# PLmodule.net
KiCad netlist of a schematic drawn in Altium Designer
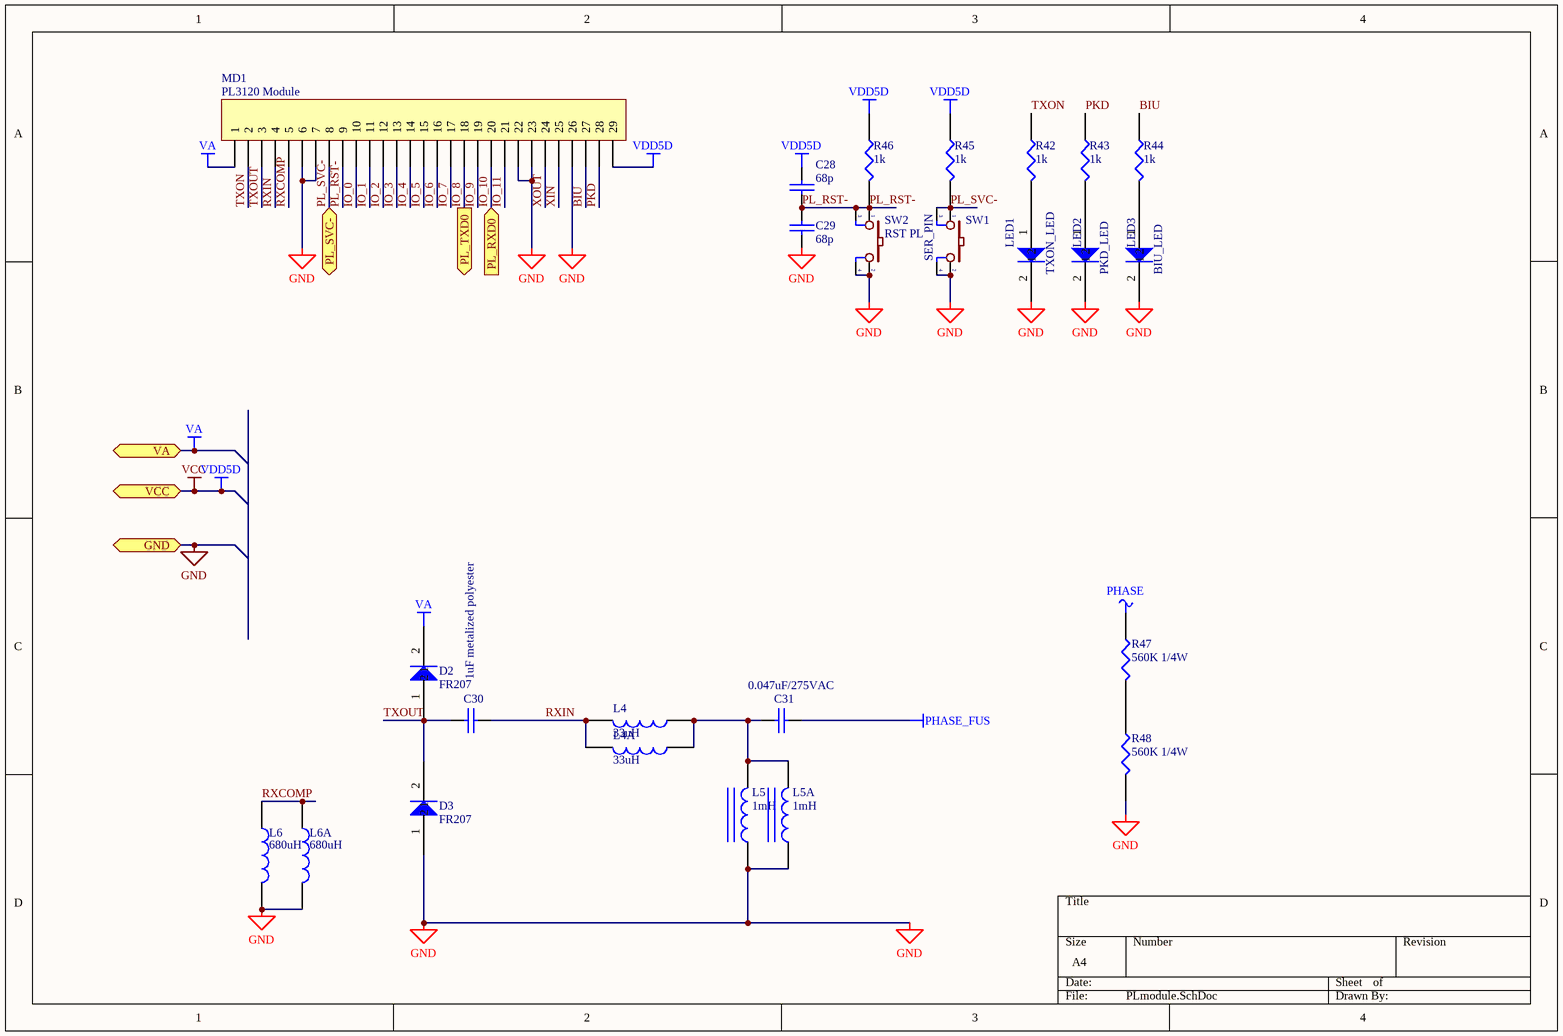
[diagram p0: PLmodule.SchDoc]

(export (version "E")
  (design (tool "Eeschema 10.0.6"))
  (components
    (comp (ref "C28")
      (value "68p")
      (footprint "C6-0805_N")
      (description "Capacitor")
      (libsource (lib "*") (part "CAP"))
    )
    (comp (ref "C29")
      (value "68p")
      (footprint "C6-0805_N")
      (description "Capacitor")
      (libsource (lib "*") (part "CAP"))
    )
    (comp (ref "C30")
      (value "1uF metalized polyester")
      (footprint "CSIP3")
      (description "Capacitor")
      (libsource (lib "*") (part "CAP"))
    )
    (comp (ref "C31")
      (value "0.047uF/275VAC")
      (footprint "100n400v")
      (description "X2 0.047uF/275VAC")
      (libsource (lib "*") (part "CAP"))
    )
    (comp (ref "D2") (value "FR207") (footprint "DO-214AA") (libsource (lib "*") (part "DIODE")))
    (comp (ref "D3") (value "FR207") (footprint "DO-214AA") (libsource (lib "*") (part "DIODE")))
    (comp (ref "L4")
      (value "33uH")
      (footprint "6D28")
      (description "0805 inductor")
      (libsource (lib "") (part "INDUCTOR_1"))
    )
    (comp (ref "L4A")
      (value "33uH")
      (footprint "Axial-0.4")
      (description "Axial inductor")
      (libsource (lib "") (part "INDUCTOR_1"))
    )
    (comp (ref "L5") (value "1mH") (footprint "6-0805_N") (libsource (lib "*") (part "INDUCTOR IRON")))
    (comp (ref "L5A") (value "1mH") (footprint "AXIAL-0.4") (libsource (lib "*") (part "INDUCTOR IRON")))
    (comp (ref "L6") (value "680uH") (footprint "6-0805_N") (libsource (lib "*") (part "INDUCTOR")))
    (comp (ref "L6A") (value "680uH") (footprint "AXIAL-0.4") (libsource (lib "*") (part "INDUCTOR")))
    (comp (ref "LED1") (value "TXON_LED") (footprint "led3mm") (libsource (lib "*") (part "DIODE")))
    (comp (ref "LED2") (value "PKD_LED") (footprint "led3mm") (libsource (lib "*") (part "DIODE")))
    (comp (ref "LED3") (value "BIU_LED") (footprint "led3mm") (libsource (lib "*") (part "DIODE")))
    (comp (ref "MD1")
      (value "PL3120 Module")
      (footprint "ECHELONMODULE")
      (description "Connector")
      (libsource (lib "*") (part "CON29"))
    )
    (comp (ref "R42") (value "1k") (footprint "6-0805_N") (libsource (lib "*") (part "RES1")))
    (comp (ref "R43") (value "1k") (footprint "6-0805_N") (libsource (lib "*") (part "RES1")))
    (comp (ref "R44") (value "1k") (footprint "6-0805_N") (libsource (lib "*") (part "RES1")))
    (comp (ref "R45") (value "1k") (footprint "6-0805_N") (libsource (lib "*") (part "RES1")))
    (comp (ref "R46") (value "1k") (footprint "6-0805_N") (libsource (lib "*") (part "RES1")))
    (comp (ref "R47") (value "560K 1/4W") (footprint "R3216[1206]") (libsource (lib "*") (part "RES1")))
    (comp (ref "R48") (value "560K 1/4W") (footprint "R3216[1206]") (libsource (lib "*") (part "RES1")))
    (comp (ref "SW1")
      (value "SER_PIN")
      (footprint "SW-4P-S")
      (description "Switch button 4 pin")
      (libsource (lib "syhaunguyen") (part "SW4-1"))
    )
    (comp (ref "SW2")
      (value "RST PL")
      (footprint "SW-4P-S")
      (description "Switch button 4 pin")
      (libsource (lib "syhaunguyen") (part "SW4-1"))
    )
  )
  (nets
    (net (code "1") (name "/BIU") (class "Default")
      (node (ref "MD1") (pin "27") (pinfunction "27_27") (pintype "passive"))
      (node (ref "R44") (pin "1") (pinfunction "1_1") (pintype "passive"))
    )
    (net (code "2") (name "/IO_0") (class "Default")
      (node (ref "MD1") (pin "10") (pinfunction "10_10") (pintype "passive"))
    )
    (net (code "3") (name "/IO_1") (class "Default")
      (node (ref "MD1") (pin "11") (pinfunction "11_11") (pintype "passive"))
    )
    (net (code "4") (name "/IO_2") (class "Default")
      (node (ref "MD1") (pin "12") (pinfunction "12_12") (pintype "passive"))
    )
    (net (code "5") (name "/IO_3") (class "Default")
      (node (ref "MD1") (pin "13") (pinfunction "13_13") (pintype "passive"))
    )
    (net (code "6") (name "/IO_4") (class "Default")
      (node (ref "MD1") (pin "14") (pinfunction "14_14") (pintype "passive"))
    )
    (net (code "7") (name "/IO_5") (class "Default")
      (node (ref "MD1") (pin "15") (pinfunction "15_15") (pintype "passive"))
    )
    (net (code "8") (name "/IO_6") (class "Default")
      (node (ref "MD1") (pin "16") (pinfunction "16_16") (pintype "passive"))
    )
    (net (code "9") (name "/IO_7") (class "Default")
      (node (ref "MD1") (pin "17") (pinfunction "17_17") (pintype "passive"))
    )
    (net (code "10") (name "/IO_8") (class "Default")
      (node (ref "MD1") (pin "18") (pinfunction "18_18") (pintype "passive"))
    )
    (net (code "11") (name "/IO_9") (class "Default")
      (node (ref "MD1") (pin "19") (pinfunction "19_19") (pintype "passive"))
    )
    (net (code "12") (name "/IO_10") (class "Default")
      (node (ref "MD1") (pin "20") (pinfunction "20_20") (pintype "passive"))
    )
    (net (code "13") (name "/IO_11") (class "Default")
      (node (ref "MD1") (pin "21") (pinfunction "21_21") (pintype "passive"))
    )
    (net (code "14") (name "/PKD") (class "Default")
      (node (ref "MD1") (pin "28") (pinfunction "28_28") (pintype "passive"))
      (node (ref "R43") (pin "1") (pinfunction "1_1") (pintype "passive"))
    )
    (net (code "15") (name "/PL_RST-") (class "Default")
      (node (ref "C28") (pin "1") (pinfunction "1_1") (pintype "passive"))
      (node (ref "C29") (pin "1") (pinfunction "1_1") (pintype "passive"))
      (node (ref "MD1") (pin "9") (pinfunction "9_9") (pintype "passive"))
      (node (ref "R46") (pin "2") (pinfunction "2_2") (pintype "passive"))
      (node (ref "SW2") (pin "1") (pinfunction "1_1") (pintype "passive"))
      (node (ref "SW2") (pin "3") (pinfunction "3_3") (pintype "passive"))
    )
    (net (code "16") (name "/PL_SVC-") (class "Default")
      (node (ref "MD1") (pin "8") (pinfunction "8_8") (pintype "passive"))
      (node (ref "R45") (pin "2") (pinfunction "2_2") (pintype "passive"))
      (node (ref "SW1") (pin "1") (pinfunction "1_1") (pintype "passive"))
      (node (ref "SW1") (pin "3") (pinfunction "3_3") (pintype "passive"))
    )
    (net (code "17") (name "/RXCOMP") (class "Default")
      (node (ref "L6") (pin "1") (pinfunction "1_1") (pintype "passive"))
      (node (ref "L6A") (pin "1") (pinfunction "1_1") (pintype "passive"))
      (node (ref "MD1") (pin "5") (pinfunction "5_5") (pintype "passive"))
    )
    (net (code "18") (name "/RXIN") (class "Default")
      (node (ref "C30") (pin "2") (pinfunction "2_2") (pintype "passive"))
      (node (ref "L4") (pin "1") (pinfunction "1_1") (pintype "passive"))
      (node (ref "L4A") (pin "1") (pinfunction "1_1") (pintype "passive"))
      (node (ref "MD1") (pin "4") (pinfunction "4_4") (pintype "passive"))
    )
    (net (code "19") (name "/TXON") (class "Default")
      (node (ref "MD1") (pin "2") (pinfunction "2_2") (pintype "passive"))
      (node (ref "R42") (pin "1") (pinfunction "1_1") (pintype "passive"))
    )
    (net (code "20") (name "/TXOUT") (class "Default")
      (node (ref "C30") (pin "1") (pinfunction "1_1") (pintype "passive"))
      (node (ref "D2") (pin "1") (pinfunction "1_1") (pintype "passive"))
      (node (ref "D3") (pin "2") (pinfunction "2_2") (pintype "passive"))
      (node (ref "MD1") (pin "3") (pinfunction "3_3") (pintype "passive"))
    )
    (net (code "21") (name "/XIN") (class "Default")
      (node (ref "MD1") (pin "25") (pinfunction "25_25") (pintype "passive"))
    )
    (net (code "22") (name "/XOUT") (class "Default")
      (node (ref "MD1") (pin "24") (pinfunction "24_24") (pintype "passive"))
    )
    (net (code "23") (name "GND") (class "Default")
      (node (ref "C29") (pin "2") (pinfunction "2_2") (pintype "passive"))
      (node (ref "D3") (pin "1") (pinfunction "1_1") (pintype "passive"))
      (node (ref "L5") (pin "2") (pinfunction "2_2") (pintype "passive"))
      (node (ref "L5A") (pin "2") (pinfunction "2_2") (pintype "passive"))
      (node (ref "L6") (pin "2") (pinfunction "2_2") (pintype "passive"))
      (node (ref "L6A") (pin "2") (pinfunction "2_2") (pintype "passive"))
      (node (ref "LED1") (pin "2") (pinfunction "2_2") (pintype "passive"))
      (node (ref "LED2") (pin "2") (pinfunction "2_2") (pintype "passive"))
      (node (ref "LED3") (pin "2") (pinfunction "2_2") (pintype "passive"))
      (node (ref "MD1") (pin "22") (pinfunction "22_22") (pintype "passive"))
      (node (ref "MD1") (pin "23") (pinfunction "23_23") (pintype "passive"))
      (node (ref "MD1") (pin "26") (pinfunction "26_26") (pintype "passive"))
      (node (ref "MD1") (pin "6") (pinfunction "6_6") (pintype "passive"))
      (node (ref "MD1") (pin "7") (pinfunction "7_7") (pintype "passive"))
      (node (ref "R48") (pin "1") (pinfunction "1_1") (pintype "passive"))
      (node (ref "SW1") (pin "2") (pinfunction "2_2") (pintype "passive"))
      (node (ref "SW1") (pin "4") (pinfunction "4_4") (pintype "passive"))
      (node (ref "SW2") (pin "2") (pinfunction "2_2") (pintype "passive"))
      (node (ref "SW2") (pin "4") (pinfunction "4_4") (pintype "passive"))
    )
    (net (code "24") (name "Net-(C31-Pad2)") (class "Default")
      (node (ref "C31") (pin "2") (pinfunction "2_2") (pintype "passive"))
      (node (ref "L4") (pin "2") (pinfunction "2_2") (pintype "passive"))
      (node (ref "L4A") (pin "2") (pinfunction "2_2") (pintype "passive"))
      (node (ref "L5") (pin "1") (pinfunction "1_1") (pintype "passive"))
      (node (ref "L5A") (pin "1") (pinfunction "1_1") (pintype "passive"))
    )
    (net (code "25") (name "Net-(LED1-Pad1)") (class "Default")
      (node (ref "LED1") (pin "1") (pinfunction "1_1") (pintype "passive"))
      (node (ref "R42") (pin "2") (pinfunction "2_2") (pintype "passive"))
    )
    (net (code "26") (name "Net-(LED2-Pad1)") (class "Default")
      (node (ref "LED2") (pin "1") (pinfunction "1_1") (pintype "passive"))
      (node (ref "R43") (pin "2") (pinfunction "2_2") (pintype "passive"))
    )
    (net (code "27") (name "Net-(LED3-Pad1)") (class "Default")
      (node (ref "LED3") (pin "1") (pinfunction "1_1") (pintype "passive"))
      (node (ref "R44") (pin "2") (pinfunction "2_2") (pintype "passive"))
    )
    (net (code "28") (name "Net-(R47-Pad1)") (class "Default")
      (node (ref "R47") (pin "1") (pinfunction "1_1") (pintype "passive"))
      (node (ref "R48") (pin "2") (pinfunction "2_2") (pintype "passive"))
    )
    (net (code "29") (name "PHASE") (class "Default")
      (node (ref "R47") (pin "2") (pinfunction "2_2") (pintype "passive"))
    )
    (net (code "30") (name "PHASE_FUS") (class "Default")
      (node (ref "C31") (pin "1") (pinfunction "1_1") (pintype "passive"))
    )
    (net (code "31") (name "VA") (class "Default")
      (node (ref "D2") (pin "2") (pinfunction "2_2") (pintype "passive"))
      (node (ref "MD1") (pin "1") (pinfunction "1_1") (pintype "passive"))
    )
    (net (code "32") (name "VCC") (class "Default")
      (node (ref "C28") (pin "2") (pinfunction "2_2") (pintype "passive"))
      (node (ref "MD1") (pin "29") (pinfunction "29_29") (pintype "passive"))
      (node (ref "R45") (pin "1") (pinfunction "1_1") (pintype "passive"))
      (node (ref "R46") (pin "1") (pinfunction "1_1") (pintype "passive"))
    )
  )
)
